# Gas_Sampler-Sensors.net
KiCad netlist of a schematic drawn in Altium Designer
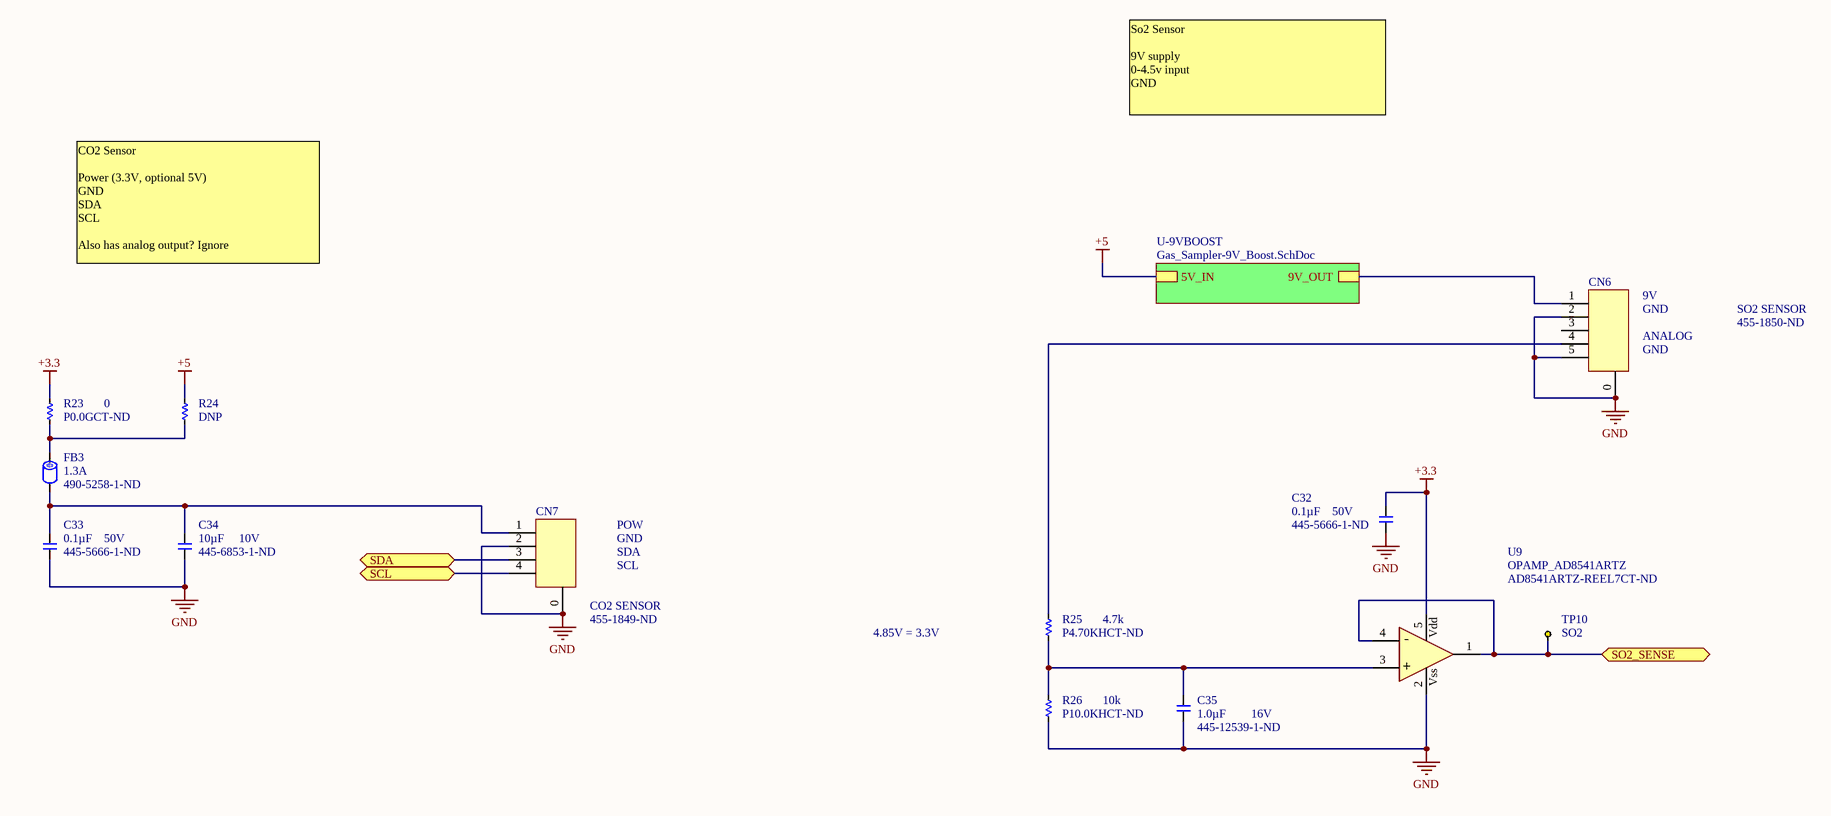
[diagram p0: Gas_Sampler-Sensors.SchDoc]

(export (version "E")
  (design (tool "Eeschema 10.0.6"))
  (components
    (comp (ref "C32")
      (value "0.1µF")
      (footprint "C0603")
      (description "CAP CER 0.1UF 50V 10% X7R 0603")
      (fields
        (field (name "MANUFACTURER") "TDK Corporation")
        (field (name "MANUFACTURER PART NUMBER") "CGA3E2X7R1H104K080AA")
        (field (name "VOLTAGE - RATED") "50V")
        (field (name "SUPPLIER PART NUMBER 1") "445-5666-1-ND")
      )
      (libsource (lib "capacitor") (part "CAP_CER_0603_0.1UF_50V_10%_X7R"))
    )
    (comp (ref "C33")
      (value "0.1µF")
      (footprint "C0603")
      (description "CAP CER 0.1UF 50V 10% X7R 0603")
      (fields
        (field (name "MANUFACTURER") "TDK Corporation")
        (field (name "MANUFACTURER PART NUMBER") "CGA3E2X7R1H104K080AA")
        (field (name "VOLTAGE - RATED") "50V")
        (field (name "SUPPLIER PART NUMBER 1") "445-5666-1-ND")
      )
      (libsource (lib "capacitor") (part "CAP_CER_0603_0.1UF_50V_10%_X7R"))
    )
    (comp (ref "C34")
      (value "10µF")
      (footprint "C0603")
      (description "CAP CER 10UF 10V X5R 0603")
      (fields
        (field (name "MANUFACTURER") "TDK Corporation")
        (field (name "MANUFACTURER PART NUMBER") "C1608X5R1A106M080AC")
        (field (name "VOLTAGE - RATED") "10V")
        (field (name "SUPPLIER PART NUMBER 1") "445-6853-1-ND")
      )
      (libsource (lib "capacitor") (part "CAP_CER_0603_10UF_10V_20%_X5R"))
    )
    (comp (ref "C35")
      (value "1.0µF")
      (footprint "C0603")
      (description "CAP CER 1UF 16V 10% X7R 0603")
      (fields
        (field (name "MANUFACTURER") "TDK Corporation")
        (field (name "MANUFACTURER PART NUMBER") "CGA3E1X7R1C105K080AC")
        (field (name "SUPPLIER PART NUMBER 1") "445-12539-1-ND")
        (field (name "VOLTAGE - RATED") "16V")
      )
      (libsource (lib "capacitor") (part "CAP_CER_0603_1UF_16V_10%_X7R"))
    )
    (comp (ref "CN6")
      (value "SO2 SENSOR")
      (footprint "JST_PA_S05B-PASK-2")
      (description "CONN HEADER PA 5POS SIDE 2MM TIN")
      (fields
        (field (name "MANUFACTURER") "JST Sales America Inc.")
        (field (name "MANUFACTURER PART NUMBER") "S05B-PASK-2(LF)(SN)")
        (field (name "SUPPLIER PART NUMBER 1") "455-1850-ND")
      )
      (libsource (lib "jst pa") (part "JST_PA_RA_TH_GUIDE_5POS"))
    )
    (comp (ref "CN7")
      (value "CO2 SENSOR")
      (footprint "JST_PA_S04B-PASK-2")
      (description "CONN HEADER PA 4POS SIDE 2MM TIN")
      (fields
        (field (name "MANUFACTURER") "JST Sales America Inc.")
        (field (name "MANUFACTURER PART NUMBER") "S04B-PASK-2(LF)(SN)")
        (field (name "SUPPLIER PART NUMBER 1") "455-1849-ND")
      )
      (libsource (lib "jst pa") (part "JST_PA_RA_TH_GUIDE_4POS"))
    )
    (comp (ref "FB3")
      (value "FERRITE_BEAD_0603_1.3A_600_OHM")
      (footprint "R0603")
      (description "FERRITE BEAD 600 OHM 0603 1LN")
      (fields
        (field (name "MANUFACTURER") "Murata Electronics North America")
        (field (name "MANUFACTURER PART NUMBER") "BLM18KG601SN1D")
        (field (name "CURRENT RATING (MAX)") "1.3A")
        (field (name "SUPPLIER PART NUMBER 1") "490-5258-1-ND")
      )
      (libsource (lib "miscellaneous") (part "FERRITE_BEAD_0603_1.3A_600_OHM"))
    )
    (comp (ref "R23")
      (value "0")
      (footprint "R0603")
      (description "RES 0.0 OHM 1/10W JUMP 0603 SMD")
      (fields
        (field (name "MANUFACTURER") "Panasonic Electronic Components")
        (field (name "MANUFACTURER PART NUMBER") "ERJ-3GEY0R00V")
        (field (name "SUPPLIER PART NUMBER 1") "P0.0GCT-ND")
      )
      (libsource (lib "resistor") (part "RES_0603_0_OHM_1/10W"))
    )
    (comp (ref "R24")
      (value "DNP")
      (footprint "R0603")
      (description "RES DNP 0603 SMD")
      (fields (field (name "PART NUMBER") "000-00000-00") (field (name "Comment") "RES_0603_DNP"))
      (libsource (lib "resistor") (part "RES_0603_DNP"))
    )
    (comp (ref "R25")
      (value "4.7k")
      (footprint "R0603")
      (description "RES 4.7K OHM 1/10W 1% 0603 SMD")
      (fields
        (field (name "MANUFACTURER") "Panasonic Electronic Components")
        (field (name "MANUFACTURER PART NUMBER") "ERJ-3EKF4701V")
        (field (name "SUPPLIER PART NUMBER 1") "P4.70KHCT-ND")
      )
      (libsource (lib "resistor") (part "RES_0603_4.7K_OHM_1/10W_1%"))
    )
    (comp (ref "R26")
      (value "10k")
      (footprint "R0603")
      (description "RES 10K OHM 1/10W 1% 0603 SMD")
      (fields
        (field (name "MANUFACTURER") "Panasonic Electronic Components")
        (field (name "MANUFACTURER PART NUMBER") "ERJ-3EKF1002V")
        (field (name "SUPPLIER PART NUMBER 1") "P10.0KHCT-ND")
      )
      (libsource (lib "resistor") (part "RES_0603_10K_OHM_1/10W_1%"))
    )
    (comp (ref "TP10")
      (value "SO2")
      (footprint "TP_KEYSTONE_5001")
      (description "PC TEST POINT TH RING")
      (fields
        (field (name "MANUFACTURER") "Keystone Electronics")
        (field (name "MANUFACTURER PART NUMBER") "5001")
      )
      (libsource (lib "miscellaneous") (part "TEST_KEYSTONE5001"))
    )
    (comp (ref "U9")
      (value "OPAMP_AD8541ARTZ")
      (footprint "5SOT23")
      (description "IC OPAMP GP R-R CMOS SOT23-5")
      (fields
        (field (name "MANUFACTURER") "Analog Devices Inc")
        (field (name "MANUFACTURER PART NUMBER") "AD8541ARTZ-REEL7")
        (field (name "SUPPLIER PART NUMBER 1") "AD8541ARTZ-REEL7CT-ND")
      )
      (libsource (lib "ic_analog") (part "OPAMP_AD8541ARTZ"))
    )
  )
  (nets
    (net (code "1") (name "+3.3") (class "Default")
      (node (ref "C32") (pin "1") (pintype "passive"))
      (node (ref "R23") (pin "2") (pintype "passive"))
      (node (ref "U9") (pin "5") (pinfunction "VDD_5") (pintype "passive"))
    )
    (net (code "2") (name "+5") (class "Default") (node (ref "R24") (pin "2") (pintype "passive")))
    (net (code "3") (name "/9V_OUT") (class "Default")
      (node (ref "CN6") (pin "1") (pinfunction "1_1") (pintype "passive"))
    )
    (net (code "4") (name "/SCL") (class "Default")
      (node (ref "CN7") (pin "4") (pinfunction "4_4") (pintype "passive"))
    )
    (net (code "5") (name "/SDA") (class "Default")
      (node (ref "CN7") (pin "3") (pinfunction "3_3") (pintype "passive"))
    )
    (net (code "6") (name "/SO2_SENSE") (class "Default")
      (node (ref "TP10") (pin "1") (pintype "passive"))
      (node (ref "U9") (pin "1") (pinfunction "OUT_1") (pintype "passive"))
      (node (ref "U9") (pin "4") (pinfunction "IN-_4") (pintype "passive"))
    )
    (net (code "7") (name "GND") (class "Default")
      (node (ref "C32") (pin "2") (pintype "passive"))
      (node (ref "C33") (pin "2") (pintype "passive"))
      (node (ref "C34") (pin "2") (pintype "passive"))
      (node (ref "C35") (pin "2") (pintype "passive"))
      (node (ref "CN6") (pin "0") (pinfunction "CHAS_0") (pintype "passive"))
      (node (ref "CN6") (pin "2") (pinfunction "2_2") (pintype "passive"))
      (node (ref "CN6") (pin "5") (pinfunction "5_5") (pintype "passive"))
      (node (ref "CN7") (pin "0") (pinfunction "CHAS_0") (pintype "passive"))
      (node (ref "CN7") (pin "2") (pinfunction "2_2") (pintype "passive"))
      (node (ref "R26") (pin "1") (pintype "passive"))
      (node (ref "U9") (pin "2") (pinfunction "VSS_2") (pintype "passive"))
    )
    (net (code "8") (name "Net-(C33-Pad1)") (class "Default")
      (node (ref "C33") (pin "1") (pintype "passive"))
      (node (ref "C34") (pin "1") (pintype "passive"))
      (node (ref "CN7") (pin "1") (pinfunction "1_1") (pintype "passive"))
      (node (ref "FB3") (pin "2") (pinfunction "2_2") (pintype "passive"))
    )
    (net (code "9") (name "Net-(CN6-Pad4)") (class "Default")
      (node (ref "CN6") (pin "4") (pinfunction "4_4") (pintype "passive"))
      (node (ref "R25") (pin "2") (pintype "passive"))
    )
    (net (code "10") (name "Net-(FB3-Pad1)") (class "Default")
      (node (ref "FB3") (pin "1") (pinfunction "1_1") (pintype "passive"))
      (node (ref "R23") (pin "1") (pintype "passive"))
      (node (ref "R24") (pin "1") (pintype "passive"))
    )
    (net (code "11") (name "Net-(U9-IN+)") (class "Default")
      (node (ref "C35") (pin "1") (pintype "passive"))
      (node (ref "R25") (pin "1") (pintype "passive"))
      (node (ref "R26") (pin "2") (pintype "passive"))
      (node (ref "U9") (pin "3") (pinfunction "IN+_3") (pintype "passive"))
    )
    (net (code "12") (name "unconnected-(CN6-Pad3)") (class "Default")
      (node (ref "CN6") (pin "3") (pinfunction "3_3") (pintype "passive"))
    )
  )
)
